# PiKVM_ATX_Adapter_v1_5.net
KiCad netlist of a schematic drawn in EAGLE
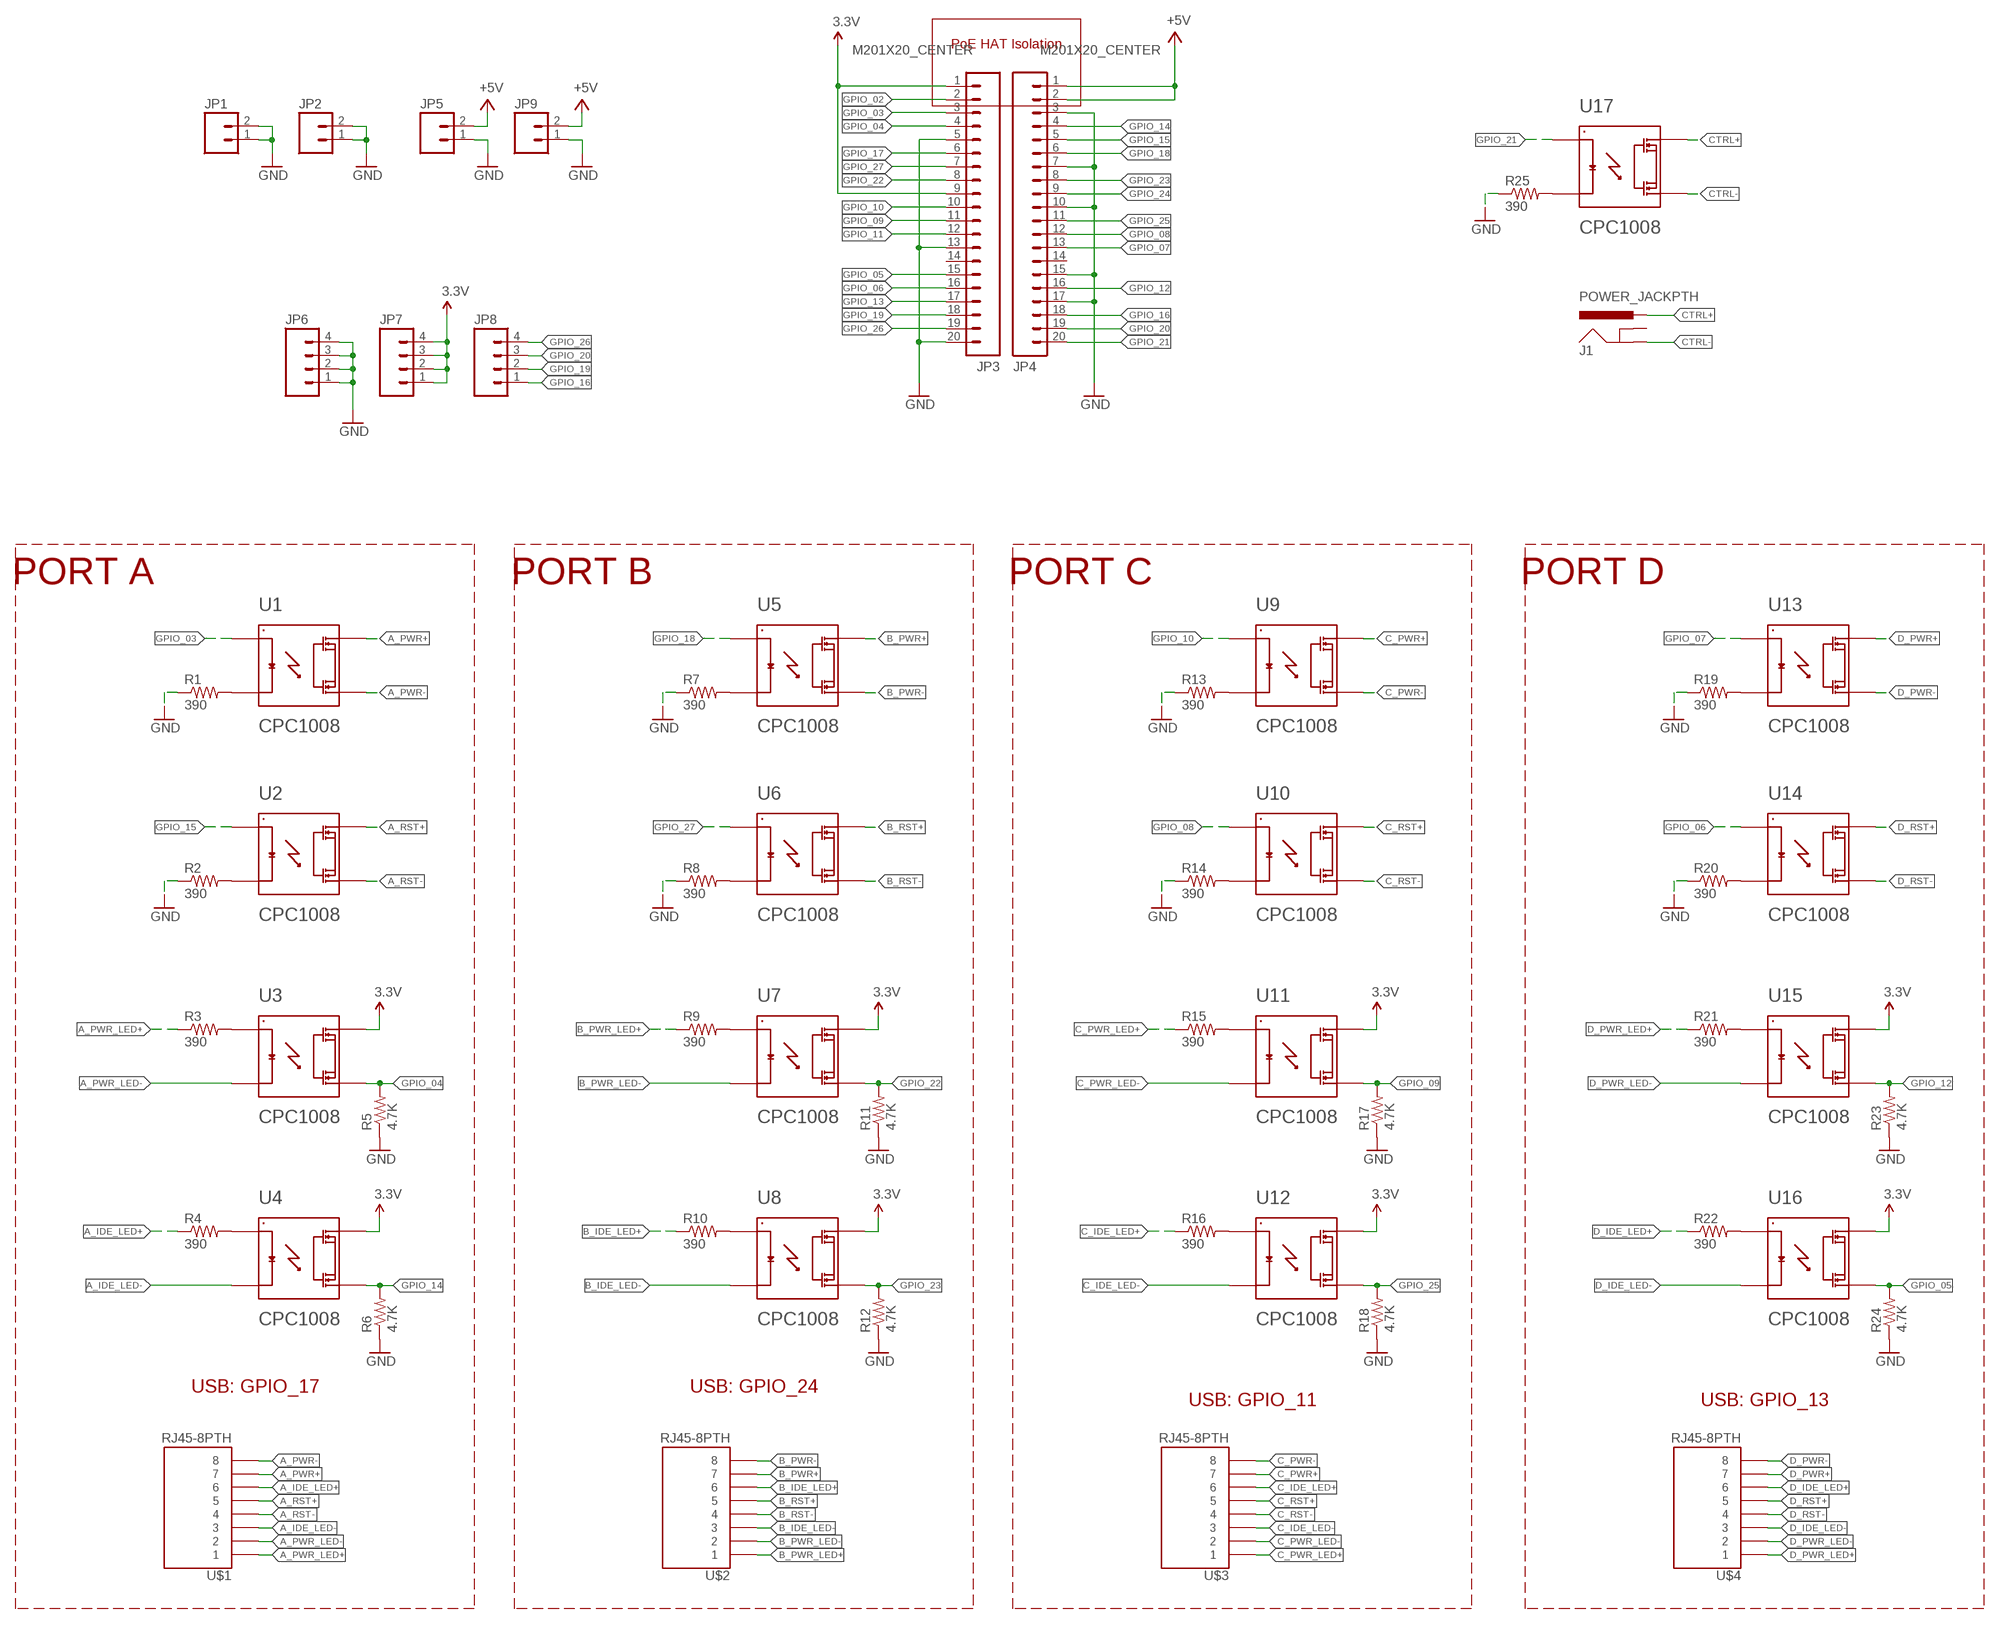
[diagram p0: schematic, sheet 1]

(export (version "E")
  (design (tool "Eeschema 10.0.6"))
  (components
    (comp (ref "J1")
      (value "POWER_JACKPTH")
      (footprint "eagle-import:POWER_JACK_PTH")
      (libsource (lib "eagle-import") (part "POWER_JACKPTH"))
    )
    (comp (ref "JP1")
      (value "M02LOCK")
      (footprint "eagle-import:1X02_LOCK")
      (libsource (lib "eagle-import") (part "M02LOCK"))
    )
    (comp (ref "JP2")
      (value "M02LOCK")
      (footprint "eagle-import:1X02_LOCK")
      (libsource (lib "eagle-import") (part "M02LOCK"))
    )
    (comp (ref "JP3")
      (value "M201X20_CENTER")
      (footprint "eagle-import:1X20_CENTER")
      (libsource (lib "eagle-import") (part "M201X20_CENTER"))
    )
    (comp (ref "JP4")
      (value "M201X20_CENTER")
      (footprint "eagle-import:1X20_CENTER")
      (libsource (lib "eagle-import") (part "M201X20_CENTER"))
    )
    (comp (ref "JP5")
      (value "M02LOCK")
      (footprint "eagle-import:1X02_LOCK")
      (libsource (lib "eagle-import") (part "M02LOCK"))
    )
    (comp (ref "JP6")
      (value "M04PTH")
      (footprint "eagle-import:1X04")
      (libsource (lib "eagle-import") (part "M04PTH"))
    )
    (comp (ref "JP7")
      (value "M04PTH")
      (footprint "eagle-import:1X04")
      (libsource (lib "eagle-import") (part "M04PTH"))
    )
    (comp (ref "JP8")
      (value "M04PTH")
      (footprint "eagle-import:1X04")
      (libsource (lib "eagle-import") (part "M04PTH"))
    )
    (comp (ref "JP9")
      (value "M02LOCK")
      (footprint "eagle-import:1X02_LOCK")
      (libsource (lib "eagle-import") (part "M02LOCK"))
    )
    (comp (ref "R1")
      (value "390")
      (footprint "eagle-import:1206")
      (libsource (lib "eagle-import") (part "RESISTOR1206"))
    )
    (comp (ref "R2")
      (value "390")
      (footprint "eagle-import:1206")
      (libsource (lib "eagle-import") (part "RESISTOR1206"))
    )
    (comp (ref "R3")
      (value "390")
      (footprint "eagle-import:1206")
      (libsource (lib "eagle-import") (part "RESISTOR1206"))
    )
    (comp (ref "R4")
      (value "390")
      (footprint "eagle-import:1206")
      (libsource (lib "eagle-import") (part "RESISTOR1206"))
    )
    (comp (ref "R5")
      (value "4.7K")
      (footprint "eagle-import:1206")
      (libsource (lib "eagle-import") (part "RESISTOR1206"))
    )
    (comp (ref "R6")
      (value "4.7K")
      (footprint "eagle-import:1206")
      (libsource (lib "eagle-import") (part "RESISTOR1206"))
    )
    (comp (ref "R7")
      (value "390")
      (footprint "eagle-import:1206")
      (libsource (lib "eagle-import") (part "RESISTOR1206"))
    )
    (comp (ref "R8")
      (value "390")
      (footprint "eagle-import:1206")
      (libsource (lib "eagle-import") (part "RESISTOR1206"))
    )
    (comp (ref "R9")
      (value "390")
      (footprint "eagle-import:1206")
      (libsource (lib "eagle-import") (part "RESISTOR1206"))
    )
    (comp (ref "R10")
      (value "390")
      (footprint "eagle-import:1206")
      (libsource (lib "eagle-import") (part "RESISTOR1206"))
    )
    (comp (ref "R11")
      (value "4.7K")
      (footprint "eagle-import:1206")
      (libsource (lib "eagle-import") (part "RESISTOR1206"))
    )
    (comp (ref "R12")
      (value "4.7K")
      (footprint "eagle-import:1206")
      (libsource (lib "eagle-import") (part "RESISTOR1206"))
    )
    (comp (ref "R13")
      (value "390")
      (footprint "eagle-import:1206")
      (libsource (lib "eagle-import") (part "RESISTOR1206"))
    )
    (comp (ref "R14")
      (value "390")
      (footprint "eagle-import:1206")
      (libsource (lib "eagle-import") (part "RESISTOR1206"))
    )
    (comp (ref "R15")
      (value "390")
      (footprint "eagle-import:1206")
      (libsource (lib "eagle-import") (part "RESISTOR1206"))
    )
    (comp (ref "R16")
      (value "390")
      (footprint "eagle-import:1206")
      (libsource (lib "eagle-import") (part "RESISTOR1206"))
    )
    (comp (ref "R17")
      (value "4.7K")
      (footprint "eagle-import:1206")
      (libsource (lib "eagle-import") (part "RESISTOR1206"))
    )
    (comp (ref "R18")
      (value "4.7K")
      (footprint "eagle-import:1206")
      (libsource (lib "eagle-import") (part "RESISTOR1206"))
    )
    (comp (ref "R19")
      (value "390")
      (footprint "eagle-import:1206")
      (libsource (lib "eagle-import") (part "RESISTOR1206"))
    )
    (comp (ref "R20")
      (value "390")
      (footprint "eagle-import:1206")
      (libsource (lib "eagle-import") (part "RESISTOR1206"))
    )
    (comp (ref "R21")
      (value "390")
      (footprint "eagle-import:1206")
      (libsource (lib "eagle-import") (part "RESISTOR1206"))
    )
    (comp (ref "R22")
      (value "390")
      (footprint "eagle-import:1206")
      (libsource (lib "eagle-import") (part "RESISTOR1206"))
    )
    (comp (ref "R23")
      (value "4.7K")
      (footprint "eagle-import:1206")
      (libsource (lib "eagle-import") (part "RESISTOR1206"))
    )
    (comp (ref "R24")
      (value "4.7K")
      (footprint "eagle-import:1206")
      (libsource (lib "eagle-import") (part "RESISTOR1206"))
    )
    (comp (ref "R25")
      (value "390")
      (footprint "eagle-import:1206")
      (libsource (lib "eagle-import") (part "RESISTOR1206"))
    )
    (comp (ref "U$1")
      (value "RJ45-8PTH")
      (footprint "eagle-import:RJ45-8")
      (libsource (lib "eagle-import") (part "RJ45-8PTH"))
    )
    (comp (ref "U$2")
      (value "RJ45-8PTH")
      (footprint "eagle-import:RJ45-8")
      (libsource (lib "eagle-import") (part "RJ45-8PTH"))
    )
    (comp (ref "U$3")
      (value "RJ45-8PTH")
      (footprint "eagle-import:RJ45-8")
      (libsource (lib "eagle-import") (part "RJ45-8PTH"))
    )
    (comp (ref "U$4")
      (value "RJ45-8PTH")
      (footprint "eagle-import:RJ45-8")
      (libsource (lib "eagle-import") (part "RJ45-8PTH"))
    )
    (comp (ref "U1")
      (value "CPC1008")
      (footprint "eagle-import:SOP-4")
      (libsource (lib "eagle-import") (part "CPC1008"))
    )
    (comp (ref "U2")
      (value "CPC1008")
      (footprint "eagle-import:SOP-4")
      (libsource (lib "eagle-import") (part "CPC1008"))
    )
    (comp (ref "U3")
      (value "CPC1008")
      (footprint "eagle-import:SOP-4")
      (libsource (lib "eagle-import") (part "CPC1008"))
    )
    (comp (ref "U4")
      (value "CPC1008")
      (footprint "eagle-import:SOP-4")
      (libsource (lib "eagle-import") (part "CPC1008"))
    )
    (comp (ref "U5")
      (value "CPC1008")
      (footprint "eagle-import:SOP-4")
      (libsource (lib "eagle-import") (part "CPC1008"))
    )
    (comp (ref "U6")
      (value "CPC1008")
      (footprint "eagle-import:SOP-4")
      (libsource (lib "eagle-import") (part "CPC1008"))
    )
    (comp (ref "U7")
      (value "CPC1008")
      (footprint "eagle-import:SOP-4")
      (libsource (lib "eagle-import") (part "CPC1008"))
    )
    (comp (ref "U8")
      (value "CPC1008")
      (footprint "eagle-import:SOP-4")
      (libsource (lib "eagle-import") (part "CPC1008"))
    )
    (comp (ref "U9")
      (value "CPC1008")
      (footprint "eagle-import:SOP-4")
      (libsource (lib "eagle-import") (part "CPC1008"))
    )
    (comp (ref "U10")
      (value "CPC1008")
      (footprint "eagle-import:SOP-4")
      (libsource (lib "eagle-import") (part "CPC1008"))
    )
    (comp (ref "U11")
      (value "CPC1008")
      (footprint "eagle-import:SOP-4")
      (libsource (lib "eagle-import") (part "CPC1008"))
    )
    (comp (ref "U12")
      (value "CPC1008")
      (footprint "eagle-import:SOP-4")
      (libsource (lib "eagle-import") (part "CPC1008"))
    )
    (comp (ref "U13")
      (value "CPC1008")
      (footprint "eagle-import:SOP-4")
      (libsource (lib "eagle-import") (part "CPC1008"))
    )
    (comp (ref "U14")
      (value "CPC1008")
      (footprint "eagle-import:SOP-4")
      (libsource (lib "eagle-import") (part "CPC1008"))
    )
    (comp (ref "U15")
      (value "CPC1008")
      (footprint "eagle-import:SOP-4")
      (libsource (lib "eagle-import") (part "CPC1008"))
    )
    (comp (ref "U16")
      (value "CPC1008")
      (footprint "eagle-import:SOP-4")
      (libsource (lib "eagle-import") (part "CPC1008"))
    )
    (comp (ref "U17")
      (value "CPC1008")
      (footprint "eagle-import:SOP-4")
      (libsource (lib "eagle-import") (part "CPC1008"))
    )
  )
  (nets
    (net (code "1") (name "+5V") (class "Default")
      (node (ref "JP4") (pin "1") (pinfunction "1_1") (pintype "passive"))
      (node (ref "JP4") (pin "2") (pinfunction "2_2") (pintype "passive"))
      (node (ref "JP5") (pin "2") (pinfunction "2_2") (pintype "passive"))
      (node (ref "JP9") (pin "2") (pinfunction "2_2") (pintype "passive"))
    )
    (net (code "2") (name "3.3V") (class "Default")
      (node (ref "JP3") (pin "1") (pinfunction "1_1") (pintype "passive"))
      (node (ref "JP3") (pin "9") (pinfunction "9_9") (pintype "passive"))
      (node (ref "JP7") (pin "1") (pinfunction "1_1") (pintype "passive"))
      (node (ref "JP7") (pin "2") (pinfunction "2_2") (pintype "passive"))
      (node (ref "JP7") (pin "3") (pinfunction "3_3") (pintype "passive"))
      (node (ref "JP7") (pin "4") (pinfunction "4_4") (pintype "passive"))
      (node (ref "U11") (pin "P$4") (pinfunction "4_P$4") (pintype "bidirectional"))
      (node (ref "U12") (pin "P$4") (pinfunction "4_P$4") (pintype "bidirectional"))
      (node (ref "U15") (pin "P$4") (pinfunction "4_P$4") (pintype "bidirectional"))
      (node (ref "U16") (pin "P$4") (pinfunction "4_P$4") (pintype "bidirectional"))
      (node (ref "U3") (pin "P$4") (pinfunction "4_P$4") (pintype "bidirectional"))
      (node (ref "U4") (pin "P$4") (pinfunction "4_P$4") (pintype "bidirectional"))
      (node (ref "U7") (pin "P$4") (pinfunction "4_P$4") (pintype "bidirectional"))
      (node (ref "U8") (pin "P$4") (pinfunction "4_P$4") (pintype "bidirectional"))
    )
    (net (code "3") (name "A_IDE_LED+") (class "Default")
      (node (ref "R4") (pin "1") (pinfunction "1_1") (pintype "passive"))
      (node (ref "U$1") (pin "6") (pinfunction "6_6") (pintype "bidirectional"))
    )
    (net (code "4") (name "A_IDE_LED-") (class "Default")
      (node (ref "U$1") (pin "3") (pinfunction "3_3") (pintype "bidirectional"))
      (node (ref "U4") (pin "P$2") (pinfunction "2_P$2") (pintype "bidirectional"))
    )
    (net (code "5") (name "A_PWR+") (class "Default")
      (node (ref "U$1") (pin "7") (pinfunction "7_7") (pintype "bidirectional"))
      (node (ref "U1") (pin "P$4") (pinfunction "4_P$4") (pintype "bidirectional"))
    )
    (net (code "6") (name "A_PWR-") (class "Default")
      (node (ref "U$1") (pin "8") (pinfunction "8_8") (pintype "bidirectional"))
      (node (ref "U1") (pin "P$3") (pinfunction "3_P$3") (pintype "bidirectional"))
    )
    (net (code "7") (name "A_PWR_LED+") (class "Default")
      (node (ref "R3") (pin "1") (pinfunction "1_1") (pintype "passive"))
      (node (ref "U$1") (pin "1") (pinfunction "1_1") (pintype "bidirectional"))
    )
    (net (code "8") (name "A_PWR_LED-") (class "Default")
      (node (ref "U$1") (pin "2") (pinfunction "2_2") (pintype "bidirectional"))
      (node (ref "U3") (pin "P$2") (pinfunction "2_P$2") (pintype "bidirectional"))
    )
    (net (code "9") (name "A_RST+") (class "Default")
      (node (ref "U$1") (pin "5") (pinfunction "5_5") (pintype "bidirectional"))
      (node (ref "U2") (pin "P$4") (pinfunction "4_P$4") (pintype "bidirectional"))
    )
    (net (code "10") (name "A_RST-") (class "Default")
      (node (ref "U$1") (pin "4") (pinfunction "4_4") (pintype "bidirectional"))
      (node (ref "U2") (pin "P$3") (pinfunction "3_P$3") (pintype "bidirectional"))
    )
    (net (code "11") (name "B_IDE_LED+") (class "Default")
      (node (ref "R10") (pin "1") (pinfunction "1_1") (pintype "passive"))
      (node (ref "U$2") (pin "6") (pinfunction "6_6") (pintype "bidirectional"))
    )
    (net (code "12") (name "B_IDE_LED-") (class "Default")
      (node (ref "U$2") (pin "3") (pinfunction "3_3") (pintype "bidirectional"))
      (node (ref "U8") (pin "P$2") (pinfunction "2_P$2") (pintype "bidirectional"))
    )
    (net (code "13") (name "B_PWR+") (class "Default")
      (node (ref "U$2") (pin "7") (pinfunction "7_7") (pintype "bidirectional"))
      (node (ref "U5") (pin "P$4") (pinfunction "4_P$4") (pintype "bidirectional"))
    )
    (net (code "14") (name "B_PWR-") (class "Default")
      (node (ref "U$2") (pin "8") (pinfunction "8_8") (pintype "bidirectional"))
      (node (ref "U5") (pin "P$3") (pinfunction "3_P$3") (pintype "bidirectional"))
    )
    (net (code "15") (name "B_PWR_LED+") (class "Default")
      (node (ref "R9") (pin "1") (pinfunction "1_1") (pintype "passive"))
      (node (ref "U$2") (pin "1") (pinfunction "1_1") (pintype "bidirectional"))
    )
    (net (code "16") (name "B_PWR_LED-") (class "Default")
      (node (ref "U$2") (pin "2") (pinfunction "2_2") (pintype "bidirectional"))
      (node (ref "U7") (pin "P$2") (pinfunction "2_P$2") (pintype "bidirectional"))
    )
    (net (code "17") (name "B_RST+") (class "Default")
      (node (ref "U$2") (pin "5") (pinfunction "5_5") (pintype "bidirectional"))
      (node (ref "U6") (pin "P$4") (pinfunction "4_P$4") (pintype "bidirectional"))
    )
    (net (code "18") (name "B_RST-") (class "Default")
      (node (ref "U$2") (pin "4") (pinfunction "4_4") (pintype "bidirectional"))
      (node (ref "U6") (pin "P$3") (pinfunction "3_P$3") (pintype "bidirectional"))
    )
    (net (code "19") (name "CTRL+") (class "Default")
      (node (ref "J1") (pin "PWR") (pinfunction "PWR_PWR") (pintype "bidirectional"))
      (node (ref "U17") (pin "P$4") (pinfunction "4_P$4") (pintype "bidirectional"))
    )
    (net (code "20") (name "CTRL-") (class "Default")
      (node (ref "J1") (pin "GND") (pinfunction "GND_GND") (pintype "bidirectional"))
      (node (ref "U17") (pin "P$3") (pinfunction "3_P$3") (pintype "bidirectional"))
    )
    (net (code "21") (name "C_IDE_LED+") (class "Default")
      (node (ref "R16") (pin "1") (pinfunction "1_1") (pintype "passive"))
      (node (ref "U$3") (pin "6") (pinfunction "6_6") (pintype "bidirectional"))
    )
    (net (code "22") (name "C_IDE_LED-") (class "Default")
      (node (ref "U$3") (pin "3") (pinfunction "3_3") (pintype "bidirectional"))
      (node (ref "U12") (pin "P$2") (pinfunction "2_P$2") (pintype "bidirectional"))
    )
    (net (code "23") (name "C_PWR+") (class "Default")
      (node (ref "U$3") (pin "7") (pinfunction "7_7") (pintype "bidirectional"))
      (node (ref "U9") (pin "P$4") (pinfunction "4_P$4") (pintype "bidirectional"))
    )
    (net (code "24") (name "C_PWR-") (class "Default")
      (node (ref "U$3") (pin "8") (pinfunction "8_8") (pintype "bidirectional"))
      (node (ref "U9") (pin "P$3") (pinfunction "3_P$3") (pintype "bidirectional"))
    )
    (net (code "25") (name "C_PWR_LED+") (class "Default")
      (node (ref "R15") (pin "1") (pinfunction "1_1") (pintype "passive"))
      (node (ref "U$3") (pin "1") (pinfunction "1_1") (pintype "bidirectional"))
    )
    (net (code "26") (name "C_PWR_LED-") (class "Default")
      (node (ref "U$3") (pin "2") (pinfunction "2_2") (pintype "bidirectional"))
      (node (ref "U11") (pin "P$2") (pinfunction "2_P$2") (pintype "bidirectional"))
    )
    (net (code "27") (name "C_RST+") (class "Default")
      (node (ref "U$3") (pin "5") (pinfunction "5_5") (pintype "bidirectional"))
      (node (ref "U10") (pin "P$4") (pinfunction "4_P$4") (pintype "bidirectional"))
    )
    (net (code "28") (name "C_RST-") (class "Default")
      (node (ref "U$3") (pin "4") (pinfunction "4_4") (pintype "bidirectional"))
      (node (ref "U10") (pin "P$3") (pinfunction "3_P$3") (pintype "bidirectional"))
    )
    (net (code "29") (name "D_IDE_LED+") (class "Default")
      (node (ref "R22") (pin "1") (pinfunction "1_1") (pintype "passive"))
      (node (ref "U$4") (pin "6") (pinfunction "6_6") (pintype "bidirectional"))
    )
    (net (code "30") (name "D_IDE_LED-") (class "Default")
      (node (ref "U$4") (pin "3") (pinfunction "3_3") (pintype "bidirectional"))
      (node (ref "U16") (pin "P$2") (pinfunction "2_P$2") (pintype "bidirectional"))
    )
    (net (code "31") (name "D_PWR+") (class "Default")
      (node (ref "U$4") (pin "7") (pinfunction "7_7") (pintype "bidirectional"))
      (node (ref "U13") (pin "P$4") (pinfunction "4_P$4") (pintype "bidirectional"))
    )
    (net (code "32") (name "D_PWR-") (class "Default")
      (node (ref "U$4") (pin "8") (pinfunction "8_8") (pintype "bidirectional"))
      (node (ref "U13") (pin "P$3") (pinfunction "3_P$3") (pintype "bidirectional"))
    )
    (net (code "33") (name "D_PWR_LED+") (class "Default")
      (node (ref "R21") (pin "1") (pinfunction "1_1") (pintype "passive"))
      (node (ref "U$4") (pin "1") (pinfunction "1_1") (pintype "bidirectional"))
    )
    (net (code "34") (name "D_PWR_LED-") (class "Default")
      (node (ref "U$4") (pin "2") (pinfunction "2_2") (pintype "bidirectional"))
      (node (ref "U15") (pin "P$2") (pinfunction "2_P$2") (pintype "bidirectional"))
    )
    (net (code "35") (name "D_RST+") (class "Default")
      (node (ref "U$4") (pin "5") (pinfunction "5_5") (pintype "bidirectional"))
      (node (ref "U14") (pin "P$4") (pinfunction "4_P$4") (pintype "bidirectional"))
    )
    (net (code "36") (name "D_RST-") (class "Default")
      (node (ref "U$4") (pin "4") (pinfunction "4_4") (pintype "bidirectional"))
      (node (ref "U14") (pin "P$3") (pinfunction "3_P$3") (pintype "bidirectional"))
    )
    (net (code "37") (name "GND") (class "Default")
      (node (ref "JP1") (pin "1") (pinfunction "1_1") (pintype "passive"))
      (node (ref "JP1") (pin "2") (pinfunction "2_2") (pintype "passive"))
      (node (ref "JP2") (pin "1") (pinfunction "1_1") (pintype "passive"))
      (node (ref "JP2") (pin "2") (pinfunction "2_2") (pintype "passive"))
      (node (ref "JP3") (pin "13") (pinfunction "13_13") (pintype "passive"))
      (node (ref "JP3") (pin "20") (pinfunction "20_20") (pintype "passive"))
      (node (ref "JP3") (pin "5") (pinfunction "5_5") (pintype "passive"))
      (node (ref "JP4") (pin "10") (pinfunction "10_10") (pintype "passive"))
      (node (ref "JP4") (pin "15") (pinfunction "15_15") (pintype "passive"))
      (node (ref "JP4") (pin "17") (pinfunction "17_17") (pintype "passive"))
      (node (ref "JP4") (pin "3") (pinfunction "3_3") (pintype "passive"))
      (node (ref "JP4") (pin "7") (pinfunction "7_7") (pintype "passive"))
      (node (ref "JP5") (pin "1") (pinfunction "1_1") (pintype "passive"))
      (node (ref "JP6") (pin "1") (pinfunction "1_1") (pintype "passive"))
      (node (ref "JP6") (pin "2") (pinfunction "2_2") (pintype "passive"))
      (node (ref "JP6") (pin "3") (pinfunction "3_3") (pintype "passive"))
      (node (ref "JP6") (pin "4") (pinfunction "4_4") (pintype "passive"))
      (node (ref "JP9") (pin "1") (pinfunction "1_1") (pintype "passive"))
      (node (ref "R1") (pin "1") (pinfunction "1_1") (pintype "passive"))
      (node (ref "R11") (pin "1") (pinfunction "1_1") (pintype "passive"))
      (node (ref "R12") (pin "1") (pinfunction "1_1") (pintype "passive"))
      (node (ref "R13") (pin "1") (pinfunction "1_1") (pintype "passive"))
      (node (ref "R14") (pin "1") (pinfunction "1_1") (pintype "passive"))
      (node (ref "R17") (pin "1") (pinfunction "1_1") (pintype "passive"))
      (node (ref "R18") (pin "1") (pinfunction "1_1") (pintype "passive"))
      (node (ref "R19") (pin "1") (pinfunction "1_1") (pintype "passive"))
      (node (ref "R2") (pin "1") (pinfunction "1_1") (pintype "passive"))
      (node (ref "R20") (pin "1") (pinfunction "1_1") (pintype "passive"))
      (node (ref "R23") (pin "1") (pinfunction "1_1") (pintype "passive"))
      (node (ref "R24") (pin "1") (pinfunction "1_1") (pintype "passive"))
      (node (ref "R25") (pin "1") (pinfunction "1_1") (pintype "passive"))
      (node (ref "R5") (pin "1") (pinfunction "1_1") (pintype "passive"))
      (node (ref "R6") (pin "1") (pinfunction "1_1") (pintype "passive"))
      (node (ref "R7") (pin "1") (pinfunction "1_1") (pintype "passive"))
      (node (ref "R8") (pin "1") (pinfunction "1_1") (pintype "passive"))
    )
    (net (code "38") (name "GPIO_02") (class "Default")
      (node (ref "JP3") (pin "2") (pinfunction "2_2") (pintype "passive"))
    )
    (net (code "39") (name "GPIO_03") (class "Default")
      (node (ref "JP3") (pin "3") (pinfunction "3_3") (pintype "passive"))
      (node (ref "U1") (pin "P$1") (pinfunction "1_P$1") (pintype "bidirectional"))
    )
    (net (code "40") (name "GPIO_04") (class "Default")
      (node (ref "JP3") (pin "4") (pinfunction "4_4") (pintype "passive"))
      (node (ref "R5") (pin "2") (pinfunction "2_2") (pintype "passive"))
      (node (ref "U3") (pin "P$3") (pinfunction "3_P$3") (pintype "bidirectional"))
    )
    (net (code "41") (name "GPIO_05") (class "Default")
      (node (ref "JP3") (pin "15") (pinfunction "15_15") (pintype "passive"))
      (node (ref "R24") (pin "2") (pinfunction "2_2") (pintype "passive"))
      (node (ref "U16") (pin "P$3") (pinfunction "3_P$3") (pintype "bidirectional"))
    )
    (net (code "42") (name "GPIO_06") (class "Default")
      (node (ref "JP3") (pin "16") (pinfunction "16_16") (pintype "passive"))
      (node (ref "U14") (pin "P$1") (pinfunction "1_P$1") (pintype "bidirectional"))
    )
    (net (code "43") (name "GPIO_07") (class "Default")
      (node (ref "JP4") (pin "13") (pinfunction "13_13") (pintype "passive"))
      (node (ref "U13") (pin "P$1") (pinfunction "1_P$1") (pintype "bidirectional"))
    )
    (net (code "44") (name "GPIO_08") (class "Default")
      (node (ref "JP4") (pin "12") (pinfunction "12_12") (pintype "passive"))
      (node (ref "U10") (pin "P$1") (pinfunction "1_P$1") (pintype "bidirectional"))
    )
    (net (code "45") (name "GPIO_09") (class "Default")
      (node (ref "JP3") (pin "11") (pinfunction "11_11") (pintype "passive"))
      (node (ref "R17") (pin "2") (pinfunction "2_2") (pintype "passive"))
      (node (ref "U11") (pin "P$3") (pinfunction "3_P$3") (pintype "bidirectional"))
    )
    (net (code "46") (name "GPIO_10") (class "Default")
      (node (ref "JP3") (pin "10") (pinfunction "10_10") (pintype "passive"))
      (node (ref "U9") (pin "P$1") (pinfunction "1_P$1") (pintype "bidirectional"))
    )
    (net (code "47") (name "GPIO_11") (class "Default")
      (node (ref "JP3") (pin "12") (pinfunction "12_12") (pintype "passive"))
    )
    (net (code "48") (name "GPIO_12") (class "Default")
      (node (ref "JP4") (pin "16") (pinfunction "16_16") (pintype "passive"))
      (node (ref "R23") (pin "2") (pinfunction "2_2") (pintype "passive"))
      (node (ref "U15") (pin "P$3") (pinfunction "3_P$3") (pintype "bidirectional"))
    )
    (net (code "49") (name "GPIO_13") (class "Default")
      (node (ref "JP3") (pin "17") (pinfunction "17_17") (pintype "passive"))
    )
    (net (code "50") (name "GPIO_14") (class "Default")
      (node (ref "JP4") (pin "4") (pinfunction "4_4") (pintype "passive"))
      (node (ref "R6") (pin "2") (pinfunction "2_2") (pintype "passive"))
      (node (ref "U4") (pin "P$3") (pinfunction "3_P$3") (pintype "bidirectional"))
    )
    (net (code "51") (name "GPIO_15") (class "Default")
      (node (ref "JP4") (pin "5") (pinfunction "5_5") (pintype "passive"))
      (node (ref "U2") (pin "P$1") (pinfunction "1_P$1") (pintype "bidirectional"))
    )
    (net (code "52") (name "GPIO_16") (class "Default")
      (node (ref "JP4") (pin "18") (pinfunction "18_18") (pintype "passive"))
      (node (ref "JP8") (pin "1") (pinfunction "1_1") (pintype "passive"))
    )
    (net (code "53") (name "GPIO_17") (class "Default")
      (node (ref "JP3") (pin "6") (pinfunction "6_6") (pintype "passive"))
    )
    (net (code "54") (name "GPIO_18") (class "Default")
      (node (ref "JP4") (pin "6") (pinfunction "6_6") (pintype "passive"))
      (node (ref "U5") (pin "P$1") (pinfunction "1_P$1") (pintype "bidirectional"))
    )
    (net (code "55") (name "GPIO_19") (class "Default")
      (node (ref "JP3") (pin "18") (pinfunction "18_18") (pintype "passive"))
      (node (ref "JP8") (pin "2") (pinfunction "2_2") (pintype "passive"))
    )
    (net (code "56") (name "GPIO_20") (class "Default")
      (node (ref "JP4") (pin "19") (pinfunction "19_19") (pintype "passive"))
      (node (ref "JP8") (pin "3") (pinfunction "3_3") (pintype "passive"))
    )
    (net (code "57") (name "GPIO_21") (class "Default")
      (node (ref "JP4") (pin "20") (pinfunction "20_20") (pintype "passive"))
      (node (ref "U17") (pin "P$1") (pinfunction "1_P$1") (pintype "bidirectional"))
    )
    (net (code "58") (name "GPIO_22") (class "Default")
      (node (ref "JP3") (pin "8") (pinfunction "8_8") (pintype "passive"))
      (node (ref "R11") (pin "2") (pinfunction "2_2") (pintype "passive"))
      (node (ref "U7") (pin "P$3") (pinfunction "3_P$3") (pintype "bidirectional"))
    )
    (net (code "59") (name "GPIO_23") (class "Default")
      (node (ref "JP4") (pin "8") (pinfunction "8_8") (pintype "passive"))
      (node (ref "R12") (pin "2") (pinfunction "2_2") (pintype "passive"))
      (node (ref "U8") (pin "P$3") (pinfunction "3_P$3") (pintype "bidirectional"))
    )
    (net (code "60") (name "GPIO_24") (class "Default")
      (node (ref "JP4") (pin "9") (pinfunction "9_9") (pintype "passive"))
    )
    (net (code "61") (name "GPIO_25") (class "Default")
      (node (ref "JP4") (pin "11") (pinfunction "11_11") (pintype "passive"))
      (node (ref "R18") (pin "2") (pinfunction "2_2") (pintype "passive"))
      (node (ref "U12") (pin "P$3") (pinfunction "3_P$3") (pintype "bidirectional"))
    )
    (net (code "62") (name "GPIO_26") (class "Default")
      (node (ref "JP3") (pin "19") (pinfunction "19_19") (pintype "passive"))
      (node (ref "JP8") (pin "4") (pinfunction "4_4") (pintype "passive"))
    )
    (net (code "63") (name "GPIO_27") (class "Default")
      (node (ref "JP3") (pin "7") (pinfunction "7_7") (pintype "passive"))
      (node (ref "U6") (pin "P$1") (pinfunction "1_P$1") (pintype "bidirectional"))
    )
    (net (code "64") (name "Net-(U1-2)") (class "Default")
      (node (ref "R1") (pin "2") (pinfunction "2_2") (pintype "passive"))
      (node (ref "U1") (pin "P$2") (pinfunction "2_P$2") (pintype "bidirectional"))
    )
    (net (code "65") (name "Net-(U2-2)") (class "Default")
      (node (ref "R2") (pin "2") (pinfunction "2_2") (pintype "passive"))
      (node (ref "U2") (pin "P$2") (pinfunction "2_P$2") (pintype "bidirectional"))
    )
    (net (code "66") (name "Net-(U3-1)") (class "Default")
      (node (ref "R3") (pin "2") (pinfunction "2_2") (pintype "passive"))
      (node (ref "U3") (pin "P$1") (pinfunction "1_P$1") (pintype "bidirectional"))
    )
    (net (code "67") (name "Net-(U4-1)") (class "Default")
      (node (ref "R4") (pin "2") (pinfunction "2_2") (pintype "passive"))
      (node (ref "U4") (pin "P$1") (pinfunction "1_P$1") (pintype "bidirectional"))
    )
    (net (code "68") (name "Net-(U5-2)") (class "Default")
      (node (ref "R7") (pin "2") (pinfunction "2_2") (pintype "passive"))
      (node (ref "U5") (pin "P$2") (pinfunction "2_P$2") (pintype "bidirectional"))
    )
    (net (code "69") (name "Net-(U6-2)") (class "Default")
      (node (ref "R8") (pin "2") (pinfunction "2_2") (pintype "passive"))
      (node (ref "U6") (pin "P$2") (pinfunction "2_P$2") (pintype "bidirectional"))
    )
    (net (code "70") (name "Net-(U7-1)") (class "Default")
      (node (ref "R9") (pin "2") (pinfunction "2_2") (pintype "passive"))
      (node (ref "U7") (pin "P$1") (pinfunction "1_P$1") (pintype "bidirectional"))
    )
    (net (code "71") (name "Net-(U8-1)") (class "Default")
      (node (ref "R10") (pin "2") (pinfunction "2_2") (pintype "passive"))
      (node (ref "U8") (pin "P$1") (pinfunction "1_P$1") (pintype "bidirectional"))
    )
    (net (code "72") (name "Net-(U9-2)") (class "Default")
      (node (ref "R13") (pin "2") (pinfunction "2_2") (pintype "passive"))
      (node (ref "U9") (pin "P$2") (pinfunction "2_P$2") (pintype "bidirectional"))
    )
    (net (code "73") (name "Net-(U10-2)") (class "Default")
      (node (ref "R14") (pin "2") (pinfunction "2_2") (pintype "passive"))
      (node (ref "U10") (pin "P$2") (pinfunction "2_P$2") (pintype "bidirectional"))
    )
    (net (code "74") (name "Net-(U11-1)") (class "Default")
      (node (ref "R15") (pin "2") (pinfunction "2_2") (pintype "passive"))
      (node (ref "U11") (pin "P$1") (pinfunction "1_P$1") (pintype "bidirectional"))
    )
    (net (code "75") (name "Net-(U12-1)") (class "Default")
      (node (ref "R16") (pin "2") (pinfunction "2_2") (pintype "passive"))
      (node (ref "U12") (pin "P$1") (pinfunction "1_P$1") (pintype "bidirectional"))
    )
    (net (code "76") (name "Net-(U13-2)") (class "Default")
      (node (ref "R19") (pin "2") (pinfunction "2_2") (pintype "passive"))
      (node (ref "U13") (pin "P$2") (pinfunction "2_P$2") (pintype "bidirectional"))
    )
    (net (code "77") (name "Net-(U14-2)") (class "Default")
      (node (ref "R20") (pin "2") (pinfunction "2_2") (pintype "passive"))
      (node (ref "U14") (pin "P$2") (pinfunction "2_P$2") (pintype "bidirectional"))
    )
    (net (code "78") (name "Net-(U15-1)") (class "Default")
      (node (ref "R21") (pin "2") (pinfunction "2_2") (pintype "passive"))
      (node (ref "U15") (pin "P$1") (pinfunction "1_P$1") (pintype "bidirectional"))
    )
    (net (code "79") (name "Net-(U16-1)") (class "Default")
      (node (ref "R22") (pin "2") (pinfunction "2_2") (pintype "passive"))
      (node (ref "U16") (pin "P$1") (pinfunction "1_P$1") (pintype "bidirectional"))
    )
    (net (code "80") (name "Net-(U17-2)") (class "Default")
      (node (ref "R25") (pin "2") (pinfunction "2_2") (pintype "passive"))
      (node (ref "U17") (pin "P$2") (pinfunction "2_P$2") (pintype "bidirectional"))
    )
    (net (code "81") (name "unconnected-(J1-PadGNDBREAK)") (class "Default")
      (node (ref "J1") (pin "GNDBREAK") (pinfunction "GNDBREAK_GNDBREAK") (pintype "bidirectional"))
    )
    (net (code "82") (name "unconnected-(JP3-Pad14)") (class "Default")
      (node (ref "JP3") (pin "14") (pinfunction "14_14") (pintype "passive"))
    )
    (net (code "83") (name "unconnected-(JP4-Pad14)") (class "Default")
      (node (ref "JP4") (pin "14") (pinfunction "14_14") (pintype "passive"))
    )
  )
)
